# Cap1.net
KiCad netlist of a schematic drawn in EAGLE
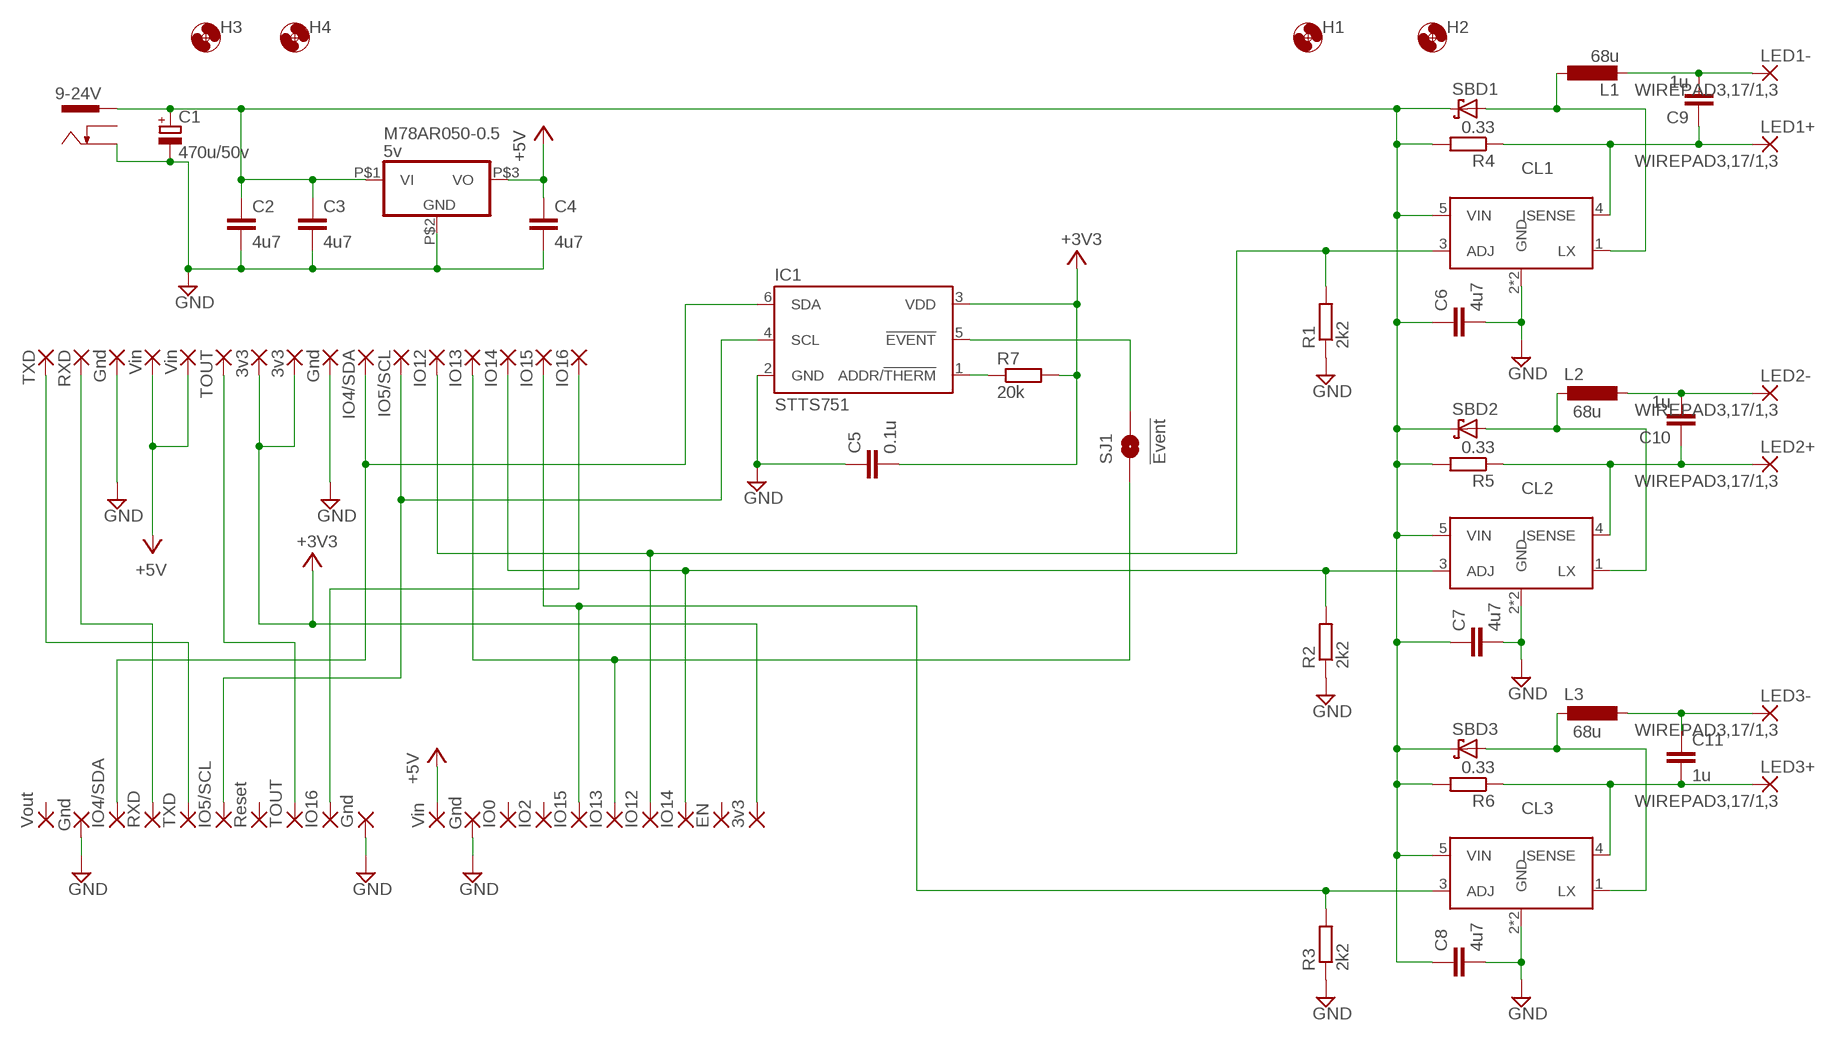
[diagram p0: schematic, sheet 1]

(export (version "E")
  (design (tool "Eeschema 10.0.6"))
  (components
    (comp (ref "0")
      (value "IO0")
      (footprint "eagle-import:1,6_0,8")
      (libsource (lib "eagle-import") (part "1,6/0,8"))
    )
    (comp (ref "2")
      (value "IO2")
      (footprint "eagle-import:1,6_0,8")
      (libsource (lib "eagle-import") (part "1,6/0,8"))
    )
    (comp (ref "3V")
      (value "3v3")
      (footprint "eagle-import:1,6_0,8")
      (libsource (lib "eagle-import") (part "1,6/0,8"))
    )
    (comp (ref "3V3")
      (value "3v3")
      (footprint "eagle-import:1,6_0,8")
      (libsource (lib "eagle-import") (part "1,6/0,8"))
    )
    (comp (ref "3V3'")
      (value "3v3")
      (footprint "eagle-import:1,6_0,8")
      (libsource (lib "eagle-import") (part "1,6/0,8"))
    )
    (comp (ref "4")
      (value "IO4/SDA")
      (footprint "eagle-import:1,6_0,8")
      (libsource (lib "eagle-import") (part "1,6/0,8"))
    )
    (comp (ref "5")
      (value "IO5/SCL")
      (footprint "eagle-import:1,6_0,8")
      (libsource (lib "eagle-import") (part "1,6/0,8"))
    )
    (comp (ref "9-24V")
      (value "DCJACK-MJ179P-R")
      (footprint "eagle-import:MJ-179P-R")
      (libsource (lib "eagle-import") (part "DCJACK-MJ179P-R"))
    )
    (comp (ref "12")
      (value "IO12")
      (footprint "eagle-import:1,6_0,8")
      (libsource (lib "eagle-import") (part "1,6/0,8"))
    )
    (comp (ref "13")
      (value "IO13")
      (footprint "eagle-import:1,6_0,8")
      (libsource (lib "eagle-import") (part "1,6/0,8"))
    )
    (comp (ref "14")
      (value "IO14")
      (footprint "eagle-import:1,6_0,8")
      (libsource (lib "eagle-import") (part "1,6/0,8"))
    )
    (comp (ref "15")
      (value "IO15")
      (footprint "eagle-import:1,6_0,8")
      (libsource (lib "eagle-import") (part "1,6/0,8"))
    )
    (comp (ref "16")
      (value "IO16")
      (footprint "eagle-import:1,6_0,8")
      (libsource (lib "eagle-import") (part "1,6/0,8"))
    )
    (comp (ref "C1")
      (value "470u/50v")
      (footprint "eagle-import:E5-13")
      (libsource (lib "eagle-import") (part "CPOL-EUE5-13"))
    )
    (comp (ref "C2")
      (value "4u7")
      (footprint "eagle-import:C0805")
      (libsource (lib "eagle-import") (part "C-EUC0805"))
    )
    (comp (ref "C3")
      (value "4u7")
      (footprint "eagle-import:C0805")
      (libsource (lib "eagle-import") (part "C-EUC0805"))
    )
    (comp (ref "C4")
      (value "4u7")
      (footprint "eagle-import:C0805")
      (libsource (lib "eagle-import") (part "C-EUC0805"))
    )
    (comp (ref "C5")
      (value "0.1u")
      (footprint "eagle-import:C0603")
      (libsource (lib "eagle-import") (part "C-EUC0603"))
    )
    (comp (ref "C6")
      (value "4u7")
      (footprint "eagle-import:C0805")
      (libsource (lib "eagle-import") (part "C-EUC0805"))
    )
    (comp (ref "C7")
      (value "4u7")
      (footprint "eagle-import:C0805")
      (libsource (lib "eagle-import") (part "C-EUC0805"))
    )
    (comp (ref "C8")
      (value "4u7")
      (footprint "eagle-import:C0805")
      (libsource (lib "eagle-import") (part "C-EUC0805"))
    )
    (comp (ref "C9")
      (value "1u")
      (footprint "eagle-import:C0603")
      (libsource (lib "eagle-import") (part "C-EUC0603"))
    )
    (comp (ref "C10")
      (value "1u")
      (footprint "eagle-import:C0603")
      (libsource (lib "eagle-import") (part "C-EUC0603"))
    )
    (comp (ref "C11")
      (value "1u")
      (footprint "eagle-import:C0603")
      (libsource (lib "eagle-import") (part "C-EUC0603"))
    )
    (comp (ref "CL1")
      (value "CL6807")
      (footprint "eagle-import:SOT89-5")
      (libsource (lib "eagle-import") (part "CL6807"))
    )
    (comp (ref "CL2")
      (value "CL6807")
      (footprint "eagle-import:SOT89-5")
      (libsource (lib "eagle-import") (part "CL6807"))
    )
    (comp (ref "CL3")
      (value "CL6807")
      (footprint "eagle-import:SOT89-5")
      (libsource (lib "eagle-import") (part "CL6807"))
    )
    (comp (ref "EN")
      (value "EN")
      (footprint "eagle-import:1,6_0,8")
      (libsource (lib "eagle-import") (part "1,6/0,8"))
    )
    (comp (ref "G")
      (value "Gnd")
      (footprint "eagle-import:1,6_0,8")
      (libsource (lib "eagle-import") (part "1,6/0,8"))
    )
    (comp (ref "G'")
      (value "Gnd")
      (footprint "eagle-import:1,6_0,8")
      (libsource (lib "eagle-import") (part "1,6/0,8"))
    )
    (comp (ref "G''")
      (value "Gnd")
      (footprint "eagle-import:1,6_0,8")
      (libsource (lib "eagle-import") (part "1,6/0,8"))
    )
    (comp (ref "GND")
      (value "Gnd")
      (footprint "eagle-import:1,6_0,8")
      (libsource (lib "eagle-import") (part "1,6/0,8"))
    )
    (comp (ref "GND1")
      (value "Gnd")
      (footprint "eagle-import:1,6_0,8")
      (libsource (lib "eagle-import") (part "1,6/0,8"))
    )
    (comp (ref "H1")
      (value "MOUNT-HOLE3.0")
      (footprint "eagle-import:3,0")
      (libsource (lib "eagle-import") (part "MOUNT-HOLE3.0"))
    )
    (comp (ref "H2")
      (value "MOUNT-HOLE3.0")
      (footprint "eagle-import:3,0")
      (libsource (lib "eagle-import") (part "MOUNT-HOLE3.0"))
    )
    (comp (ref "H3")
      (value "MOUNT-HOLE3.0")
      (footprint "eagle-import:3,0")
      (libsource (lib "eagle-import") (part "MOUNT-HOLE3.0"))
    )
    (comp (ref "H4")
      (value "MOUNT-HOLE3.0")
      (footprint "eagle-import:3,0")
      (libsource (lib "eagle-import") (part "MOUNT-HOLE3.0"))
    )
    (comp (ref "IC1")
      (value "STTS751")
      (footprint "eagle-import:SOT23-6")
      (libsource (lib "eagle-import") (part "STTS751-SOT-23-6"))
    )
    (comp (ref "IO4/SDA")
      (value "IO4/SDA")
      (footprint "eagle-import:1,6_0,8")
      (libsource (lib "eagle-import") (part "1,6/0,8"))
    )
    (comp (ref "IO5/SCL")
      (value "IO5/SCL")
      (footprint "eagle-import:1,6_0,8")
      (libsource (lib "eagle-import") (part "1,6/0,8"))
    )
    (comp (ref "IO12-CH1")
      (value "IO12")
      (footprint "eagle-import:1,6_0,8")
      (libsource (lib "eagle-import") (part "1,6/0,8"))
    )
    (comp (ref "IO13'")
      (value "IO13")
      (footprint "eagle-import:1,6_0,8")
      (libsource (lib "eagle-import") (part "1,6/0,8"))
    )
    (comp (ref "IO14-CH2")
      (value "IO14")
      (footprint "eagle-import:1,6_0,8")
      (libsource (lib "eagle-import") (part "1,6/0,8"))
    )
    (comp (ref "IO15-CH3")
      (value "IO15")
      (footprint "eagle-import:1,6_0,8")
      (libsource (lib "eagle-import") (part "1,6/0,8"))
    )
    (comp (ref "IO16")
      (value "IO16")
      (footprint "eagle-import:1,6_0,8")
      (libsource (lib "eagle-import") (part "1,6/0,8"))
    )
    (comp (ref "L1")
      (value "68u")
      (footprint "eagle-import:NR10050")
      (libsource (lib "eagle-import") (part "NR10050NR10050"))
    )
    (comp (ref "L2")
      (value "68u")
      (footprint "eagle-import:NR10050")
      (libsource (lib "eagle-import") (part "NR10050NR10050"))
    )
    (comp (ref "L3")
      (value "68u")
      (footprint "eagle-import:NR10050")
      (libsource (lib "eagle-import") (part "NR10050NR10050"))
    )
    (comp (ref "LED1+")
      (value "WIREPAD3,17/1,3")
      (footprint "eagle-import:3,17_1,3")
      (libsource (lib "eagle-import") (part "WIREPAD3,17/1,3"))
    )
    (comp (ref "LED1-")
      (value "WIREPAD3,17/1,3")
      (footprint "eagle-import:3,17_1,3")
      (libsource (lib "eagle-import") (part "WIREPAD3,17/1,3"))
    )
    (comp (ref "LED2+")
      (value "WIREPAD3,17/1,3")
      (footprint "eagle-import:3,17_1,3")
      (libsource (lib "eagle-import") (part "WIREPAD3,17/1,3"))
    )
    (comp (ref "LED2-")
      (value "WIREPAD3,17/1,3")
      (footprint "eagle-import:3,17_1,3")
      (libsource (lib "eagle-import") (part "WIREPAD3,17/1,3"))
    )
    (comp (ref "LED3+")
      (value "WIREPAD3,17/1,3")
      (footprint "eagle-import:3,17_1,3")
      (libsource (lib "eagle-import") (part "WIREPAD3,17/1,3"))
    )
    (comp (ref "LED3-")
      (value "WIREPAD3,17/1,3")
      (footprint "eagle-import:3,17_1,3")
      (libsource (lib "eagle-import") (part "WIREPAD3,17/1,3"))
    )
    (comp (ref "M78AR050-0.5")
      (value "5v")
      (footprint "eagle-import:M78AR")
      (libsource (lib "eagle-import") (part "M78AR033033-0.5"))
    )
    (comp (ref "R1")
      (value "2k2")
      (footprint "eagle-import:R0603")
      (libsource (lib "eagle-import") (part "R-EU_R0603"))
    )
    (comp (ref "R2")
      (value "2k2")
      (footprint "eagle-import:R0603")
      (libsource (lib "eagle-import") (part "R-EU_R0603"))
    )
    (comp (ref "R3")
      (value "2k2")
      (footprint "eagle-import:R0603")
      (libsource (lib "eagle-import") (part "R-EU_R0603"))
    )
    (comp (ref "R4")
      (value "0.33")
      (footprint "eagle-import:R3225")
      (libsource (lib "eagle-import") (part "R-EU_R3225"))
    )
    (comp (ref "R5")
      (value "0.33")
      (footprint "eagle-import:R3225")
      (libsource (lib "eagle-import") (part "R-EU_R3225"))
    )
    (comp (ref "R6")
      (value "0.33")
      (footprint "eagle-import:R3225")
      (libsource (lib "eagle-import") (part "R-EU_R3225"))
    )
    (comp (ref "R7")
      (value "20k")
      (footprint "eagle-import:R0603")
      (libsource (lib "eagle-import") (part "R-EU_R0603"))
    )
    (comp (ref "RS")
      (value "Reset")
      (footprint "eagle-import:1,6_0,8")
      (libsource (lib "eagle-import") (part "1,6/0,8"))
    )
    (comp (ref "RX")
      (value "RXD")
      (footprint "eagle-import:1,6_0,8")
      (libsource (lib "eagle-import") (part "1,6/0,8"))
    )
    (comp (ref "RXD")
      (value "RXD")
      (footprint "eagle-import:1,6_0,8")
      (libsource (lib "eagle-import") (part "1,6/0,8"))
    )
    (comp (ref "SBD1")
      (value "SS2040FL2SS2040FL")
      (footprint "eagle-import:SOD-123FL")
      (libsource (lib "eagle-import") (part "SS2040FLSS2040FL2"))
    )
    (comp (ref "SBD2")
      (value "SS2040FL2SS2040FL")
      (footprint "eagle-import:SOD-123FL")
      (libsource (lib "eagle-import") (part "SS2040FLSS2040FL2"))
    )
    (comp (ref "SBD3")
      (value "SS2040FL2SS2040FL")
      (footprint "eagle-import:SOD-123FL")
      (libsource (lib "eagle-import") (part "SS2040FLSS2040FL2"))
    )
    (comp (ref "SJ1")
      (value "!Event")
      (footprint "eagle-import:SJ_2S-NO")
      (libsource (lib "eagle-import") (part "SOLDERJUMPERNO"))
    )
    (comp (ref "TO")
      (value "TOUT")
      (footprint "eagle-import:1,6_0,8")
      (libsource (lib "eagle-import") (part "1,6/0,8"))
    )
    (comp (ref "TOUT")
      (value "TOUT")
      (footprint "eagle-import:1,6_0,8")
      (libsource (lib "eagle-import") (part "1,6/0,8"))
    )
    (comp (ref "TX")
      (value "TXD")
      (footprint "eagle-import:1,6_0,8")
      (libsource (lib "eagle-import") (part "1,6/0,8"))
    )
    (comp (ref "TXD")
      (value "TXD")
      (footprint "eagle-import:1,6_0,8")
      (libsource (lib "eagle-import") (part "1,6/0,8"))
    )
    (comp (ref "VI")
      (value "Vin")
      (footprint "eagle-import:1,6_0,8")
      (libsource (lib "eagle-import") (part "1,6/0,8"))
    )
    (comp (ref "VIN")
      (value "Vin")
      (footprint "eagle-import:1,6_0,8")
      (libsource (lib "eagle-import") (part "1,6/0,8"))
    )
    (comp (ref "VIN'")
      (value "Vin")
      (footprint "eagle-import:1,6_0,8")
      (libsource (lib "eagle-import") (part "1,6/0,8"))
    )
    (comp (ref "VO")
      (value "Vout")
      (footprint "eagle-import:1,6_0,8")
      (libsource (lib "eagle-import") (part "1,6/0,8"))
    )
  )
  (nets
    (net (code "1") (name "+3V3") (class "Default")
      (node (ref "3V") (pin "1") (pinfunction "P_1") (pintype "passive"))
      (node (ref "3V3") (pin "1") (pinfunction "P_1") (pintype "passive"))
      (node (ref "3V3'") (pin "1") (pinfunction "P_1") (pintype "passive"))
      (node (ref "C5") (pin "2") (pinfunction "2_2") (pintype "passive"))
      (node (ref "IC1") (pin "3") (pinfunction "VDD_3") (pintype "power_in"))
      (node (ref "R7") (pin "2") (pinfunction "2_2") (pintype "passive"))
    )
    (net (code "2") (name "+5V") (class "Default")
      (node (ref "C4") (pin "1") (pinfunction "1_1") (pintype "passive"))
      (node (ref "M78AR050-0.5") (pin "P$3") (pinfunction "VO_P$3") (pintype "passive"))
      (node (ref "VI") (pin "1") (pinfunction "P_1") (pintype "passive"))
      (node (ref "VIN") (pin "1") (pinfunction "P_1") (pintype "passive"))
      (node (ref "VIN'") (pin "1") (pinfunction "P_1") (pintype "passive"))
    )
    (net (code "3") (name "GND") (class "Default")
      (node (ref "9-24V") (pin "2") (pinfunction "2_2") (pintype "passive"))
      (node (ref "C1") (pin "-") (pinfunction "-_-") (pintype "passive"))
      (node (ref "C2") (pin "2") (pinfunction "2_2") (pintype "passive"))
      (node (ref "C3") (pin "2") (pinfunction "2_2") (pintype "passive"))
      (node (ref "C4") (pin "2") (pinfunction "2_2") (pintype "passive"))
      (node (ref "C5") (pin "1") (pinfunction "1_1") (pintype "passive"))
      (node (ref "C6") (pin "2") (pinfunction "2_2") (pintype "passive"))
      (node (ref "C7") (pin "2") (pinfunction "2_2") (pintype "passive"))
      (node (ref "C8") (pin "2") (pinfunction "2_2") (pintype "passive"))
      (node (ref "CL1") (pin "2") (pinfunction "GND_2") (pintype "passive"))
      (node (ref "CL1") (pin "2@TAB") (pinfunction "GND_2@TAB") (pintype "passive"))
      (node (ref "CL2") (pin "2") (pinfunction "GND_2") (pintype "passive"))
      (node (ref "CL2") (pin "2@TAB") (pinfunction "GND_2@TAB") (pintype "passive"))
      (node (ref "CL3") (pin "2") (pinfunction "GND_2") (pintype "passive"))
      (node (ref "CL3") (pin "2@TAB") (pinfunction "GND_2@TAB") (pintype "passive"))
      (node (ref "G") (pin "1") (pinfunction "P_1") (pintype "passive"))
      (node (ref "G'") (pin "1") (pinfunction "P_1") (pintype "passive"))
      (node (ref "G''") (pin "1") (pinfunction "P_1") (pintype "passive"))
      (node (ref "GND") (pin "1") (pinfunction "P_1") (pintype "passive"))
      (node (ref "GND1") (pin "1") (pinfunction "P_1") (pintype "passive"))
      (node (ref "IC1") (pin "2") (pinfunction "GND_2") (pintype "power_in"))
      (node (ref "M78AR050-0.5") (pin "P$2") (pinfunction "GND_P$2") (pintype "passive"))
      (node (ref "R1") (pin "1") (pinfunction "1_1") (pintype "passive"))
      (node (ref "R2") (pin "1") (pinfunction "1_1") (pintype "passive"))
      (node (ref "R3") (pin "1") (pinfunction "1_1") (pintype "passive"))
    )
    (net (code "4") (name "Net-(4-P)") (class "Default")
      (node (ref "4") (pin "1") (pinfunction "P_1") (pintype "passive"))
      (node (ref "IC1") (pin "6") (pinfunction "SDA_6") (pintype "bidirectional"))
      (node (ref "IO4/SDA") (pin "1") (pinfunction "P_1") (pintype "passive"))
    )
    (net (code "5") (name "Net-(5-P)") (class "Default")
      (node (ref "5") (pin "1") (pinfunction "P_1") (pintype "passive"))
      (node (ref "IC1") (pin "4") (pinfunction "SCL_4") (pintype "bidirectional"))
      (node (ref "IO5/SCL") (pin "1") (pinfunction "P_1") (pintype "passive"))
    )
    (net (code "6") (name "Net-(12-P)") (class "Default")
      (node (ref "12") (pin "1") (pinfunction "P_1") (pintype "passive"))
      (node (ref "CL1") (pin "3") (pinfunction "ADJ_3") (pintype "passive"))
      (node (ref "IO12-CH1") (pin "1") (pinfunction "P_1") (pintype "passive"))
      (node (ref "R1") (pin "2") (pinfunction "2_2") (pintype "passive"))
    )
    (net (code "7") (name "Net-(13-P)") (class "Default")
      (node (ref "13") (pin "1") (pinfunction "P_1") (pintype "passive"))
      (node (ref "IO13'") (pin "1") (pinfunction "P_1") (pintype "passive"))
      (node (ref "SJ1") (pin "1") (pinfunction "1_1") (pintype "passive"))
    )
    (net (code "8") (name "Net-(14-P)") (class "Default")
      (node (ref "14") (pin "1") (pinfunction "P_1") (pintype "passive"))
      (node (ref "CL2") (pin "3") (pinfunction "ADJ_3") (pintype "passive"))
      (node (ref "IO14-CH2") (pin "1") (pinfunction "P_1") (pintype "passive"))
      (node (ref "R2") (pin "2") (pinfunction "2_2") (pintype "passive"))
    )
    (net (code "9") (name "Net-(15-P)") (class "Default")
      (node (ref "15") (pin "1") (pinfunction "P_1") (pintype "passive"))
      (node (ref "CL3") (pin "3") (pinfunction "ADJ_3") (pintype "passive"))
      (node (ref "IO15-CH3") (pin "1") (pinfunction "P_1") (pintype "passive"))
      (node (ref "R3") (pin "2") (pinfunction "2_2") (pintype "passive"))
    )
    (net (code "10") (name "Net-(16-P)") (class "Default")
      (node (ref "16") (pin "1") (pinfunction "P_1") (pintype "passive"))
      (node (ref "IO16") (pin "1") (pinfunction "P_1") (pintype "passive"))
    )
    (net (code "11") (name "Net-(CL1-ISENSE)") (class "Default")
      (node (ref "C9") (pin "1") (pinfunction "1_1") (pintype "passive"))
      (node (ref "CL1") (pin "4") (pinfunction "ISENSE_4") (pintype "passive"))
      (node (ref "LED1+") (pin "1") (pinfunction "P_1") (pintype "passive"))
      (node (ref "R4") (pin "1") (pinfunction "1_1") (pintype "passive"))
    )
    (net (code "12") (name "Net-(CL1-LX)") (class "Default")
      (node (ref "CL1") (pin "1") (pinfunction "LX_1") (pintype "passive"))
      (node (ref "L1") (pin "P$1") (pinfunction "1_P$1") (pintype "passive"))
      (node (ref "SBD1") (pin "A") (pinfunction "A_A") (pintype "passive"))
    )
    (net (code "13") (name "Net-(CL1-VIN)") (class "Default")
      (node (ref "9-24V") (pin "1") (pinfunction "1_1") (pintype "passive"))
      (node (ref "C1") (pin "+") (pinfunction "+_+") (pintype "passive"))
      (node (ref "C2") (pin "1") (pinfunction "1_1") (pintype "passive"))
      (node (ref "C3") (pin "1") (pinfunction "1_1") (pintype "passive"))
      (node (ref "C6") (pin "1") (pinfunction "1_1") (pintype "passive"))
      (node (ref "C7") (pin "1") (pinfunction "1_1") (pintype "passive"))
      (node (ref "C8") (pin "1") (pinfunction "1_1") (pintype "passive"))
      (node (ref "CL1") (pin "5") (pinfunction "VIN_5") (pintype "passive"))
      (node (ref "CL2") (pin "5") (pinfunction "VIN_5") (pintype "passive"))
      (node (ref "CL3") (pin "5") (pinfunction "VIN_5") (pintype "passive"))
      (node (ref "M78AR050-0.5") (pin "P$1") (pinfunction "VI_P$1") (pintype "input"))
      (node (ref "R4") (pin "2") (pinfunction "2_2") (pintype "passive"))
      (node (ref "R5") (pin "2") (pinfunction "2_2") (pintype "passive"))
      (node (ref "R6") (pin "2") (pinfunction "2_2") (pintype "passive"))
      (node (ref "SBD1") (pin "C") (pinfunction "C_C") (pintype "passive"))
      (node (ref "SBD2") (pin "C") (pinfunction "C_C") (pintype "passive"))
      (node (ref "SBD3") (pin "C") (pinfunction "C_C") (pintype "passive"))
    )
    (net (code "14") (name "Net-(CL2-ISENSE)") (class "Default")
      (node (ref "C10") (pin "1") (pinfunction "1_1") (pintype "passive"))
      (node (ref "CL2") (pin "4") (pinfunction "ISENSE_4") (pintype "passive"))
      (node (ref "LED2+") (pin "1") (pinfunction "P_1") (pintype "passive"))
      (node (ref "R5") (pin "1") (pinfunction "1_1") (pintype "passive"))
    )
    (net (code "15") (name "Net-(CL2-LX)") (class "Default")
      (node (ref "CL2") (pin "1") (pinfunction "LX_1") (pintype "passive"))
      (node (ref "L2") (pin "P$1") (pinfunction "1_P$1") (pintype "passive"))
      (node (ref "SBD2") (pin "A") (pinfunction "A_A") (pintype "passive"))
    )
    (net (code "16") (name "Net-(CL3-ISENSE)") (class "Default")
      (node (ref "C11") (pin "2") (pinfunction "2_2") (pintype "passive"))
      (node (ref "CL3") (pin "4") (pinfunction "ISENSE_4") (pintype "passive"))
      (node (ref "LED3+") (pin "1") (pinfunction "P_1") (pintype "passive"))
      (node (ref "R6") (pin "1") (pinfunction "1_1") (pintype "passive"))
    )
    (net (code "17") (name "Net-(CL3-LX)") (class "Default")
      (node (ref "CL3") (pin "1") (pinfunction "LX_1") (pintype "passive"))
      (node (ref "L3") (pin "P$1") (pinfunction "1_P$1") (pintype "passive"))
      (node (ref "SBD3") (pin "A") (pinfunction "A_A") (pintype "passive"))
    )
    (net (code "18") (name "Net-(IC1-ADDR{slash}~{THERM})") (class "Default")
      (node (ref "IC1") (pin "1") (pinfunction "ADDR/~{THERM}_1") (pintype "output"))
      (node (ref "R7") (pin "1") (pinfunction "1_1") (pintype "passive"))
    )
    (net (code "19") (name "Net-(IC1-~{EVENT})") (class "Default")
      (node (ref "IC1") (pin "5") (pinfunction "~{EVENT}_5") (pintype "output"))
      (node (ref "SJ1") (pin "2") (pinfunction "2_2") (pintype "passive"))
    )
    (net (code "20") (name "Net-(L1-2)") (class "Default")
      (node (ref "C9") (pin "2") (pinfunction "2_2") (pintype "passive"))
      (node (ref "L1") (pin "P$2") (pinfunction "2_P$2") (pintype "passive"))
      (node (ref "LED1-") (pin "1") (pinfunction "P_1") (pintype "passive"))
    )
    (net (code "21") (name "Net-(L2-2)") (class "Default")
      (node (ref "C10") (pin "2") (pinfunction "2_2") (pintype "passive"))
      (node (ref "L2") (pin "P$2") (pinfunction "2_P$2") (pintype "passive"))
      (node (ref "LED2-") (pin "1") (pinfunction "P_1") (pintype "passive"))
    )
    (net (code "22") (name "Net-(L3-2)") (class "Default")
      (node (ref "C11") (pin "1") (pinfunction "1_1") (pintype "passive"))
      (node (ref "L3") (pin "P$2") (pinfunction "2_P$2") (pintype "passive"))
      (node (ref "LED3-") (pin "1") (pinfunction "P_1") (pintype "passive"))
    )
    (net (code "23") (name "Net-(RX-P)") (class "Default")
      (node (ref "RX") (pin "1") (pinfunction "P_1") (pintype "passive"))
      (node (ref "RXD") (pin "1") (pinfunction "P_1") (pintype "passive"))
    )
    (net (code "24") (name "Net-(TO-P)") (class "Default")
      (node (ref "TO") (pin "1") (pinfunction "P_1") (pintype "passive"))
      (node (ref "TOUT") (pin "1") (pinfunction "P_1") (pintype "passive"))
    )
    (net (code "25") (name "Net-(TX-P)") (class "Default")
      (node (ref "TX") (pin "1") (pinfunction "P_1") (pintype "passive"))
      (node (ref "TXD") (pin "1") (pinfunction "P_1") (pintype "passive"))
    )
    (net (code "26") (name "unconnected-(0-P-Pad1)") (class "Default")
      (node (ref "0") (pin "1") (pinfunction "P_1") (pintype "passive"))
    )
    (net (code "27") (name "unconnected-(2-P-Pad1)") (class "Default")
      (node (ref "2") (pin "1") (pinfunction "P_1") (pintype "passive"))
    )
    (net (code "28") (name "unconnected-(9-24V-Pad3)") (class "Default")
      (node (ref "9-24V") (pin "3") (pinfunction "3_3") (pintype "passive"))
    )
    (net (code "29") (name "unconnected-(EN-P-Pad1)") (class "Default")
      (node (ref "EN") (pin "1") (pinfunction "P_1") (pintype "passive"))
    )
    (net (code "30") (name "unconnected-(RS-P-Pad1)") (class "Default")
      (node (ref "RS") (pin "1") (pinfunction "P_1") (pintype "passive"))
    )
    (net (code "31") (name "unconnected-(VO-P-Pad1)") (class "Default")
      (node (ref "VO") (pin "1") (pinfunction "P_1") (pintype "passive"))
    )
  )
)
